# LED_Light_RS232_ZG.net
KiCad netlist of a schematic drawn in EAGLE
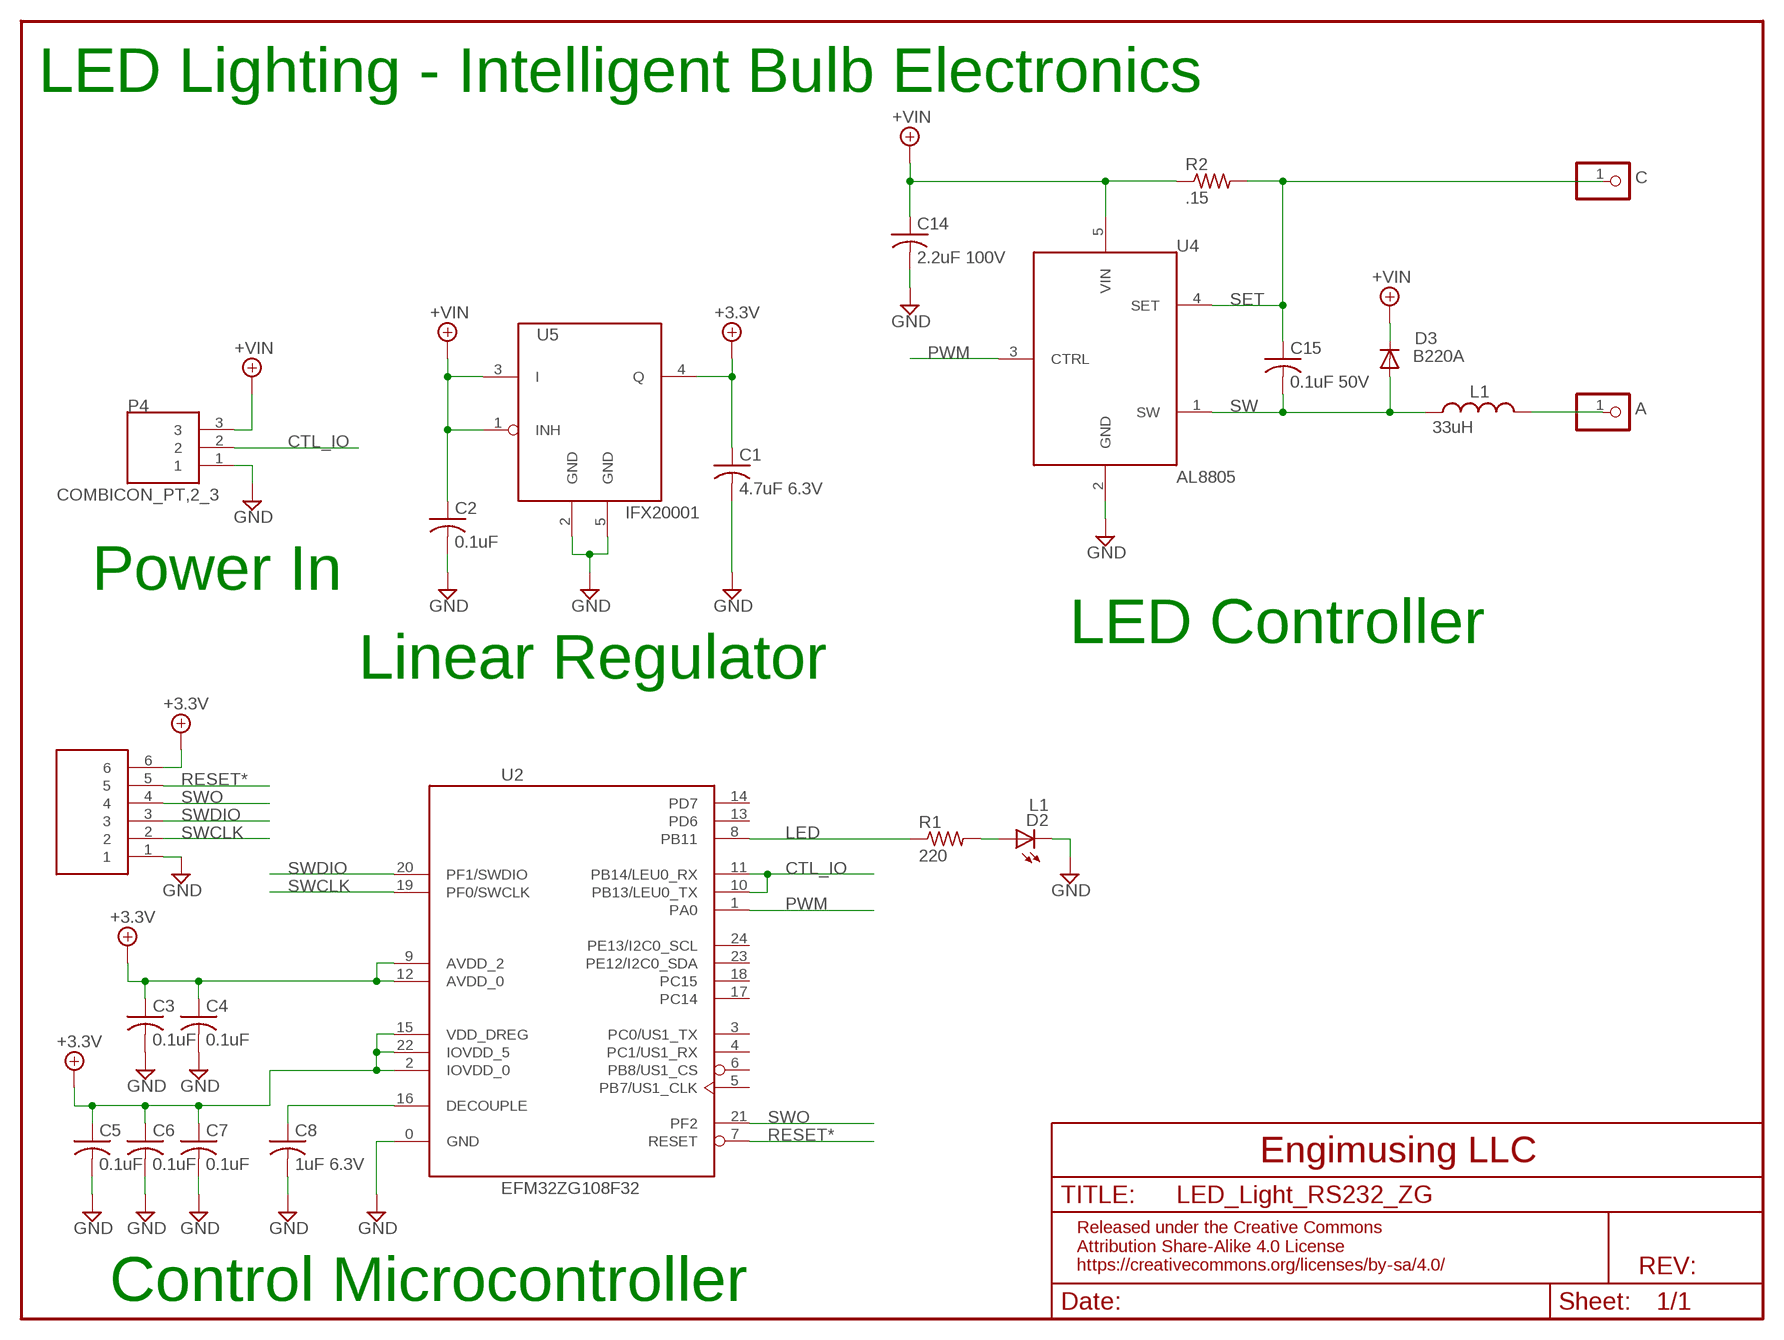
[diagram p0: schematic, sheet 1]

(export (version "E")
  (design (tool "Eeschema 10.0.6"))
  (components
    (comp (ref "A")
      (value "PINHD-1X1")
      (footprint "eagle-import:1X01")
      (libsource (lib "eagle-import") (part "PINHD-1X1"))
    )
    (comp (ref "C")
      (value "PINHD-1X1")
      (footprint "eagle-import:1X01")
      (libsource (lib "eagle-import") (part "PINHD-1X1"))
    )
    (comp (ref "C1")
      (value "4.7uF 6.3V")
      (footprint "eagle-import:C0603")
      (libsource (lib "eagle-import") (part "C-USC0603"))
    )
    (comp (ref "C2")
      (value "0.1uF")
      (footprint "eagle-import:C0603")
      (libsource (lib "eagle-import") (part "C-USC0603"))
    )
    (comp (ref "C3")
      (value "0.1uF")
      (footprint "eagle-import:C0402")
      (libsource (lib "eagle-import") (part "cc_rcl_C-USC0402"))
    )
    (comp (ref "C4")
      (value "0.1uF")
      (footprint "eagle-import:C0402")
      (libsource (lib "eagle-import") (part "cc_rcl_C-USC0402"))
    )
    (comp (ref "C5")
      (value "0.1uF")
      (footprint "eagle-import:C0402")
      (libsource (lib "eagle-import") (part "cc_rcl_C-USC0402"))
    )
    (comp (ref "C6")
      (value "0.1uF")
      (footprint "eagle-import:C0402")
      (libsource (lib "eagle-import") (part "cc_rcl_C-USC0402"))
    )
    (comp (ref "C7")
      (value "0.1uF")
      (footprint "eagle-import:C0402")
      (libsource (lib "eagle-import") (part "cc_rcl_C-USC0402"))
    )
    (comp (ref "C8")
      (value "1uF 6.3V")
      (footprint "eagle-import:C0603")
      (libsource (lib "eagle-import") (part "C-USC0603"))
    )
    (comp (ref "C14")
      (value "2.2uF 100V")
      (footprint "eagle-import:C1210K")
      (libsource (lib "eagle-import") (part "C-USC1210K"))
    )
    (comp (ref "C15")
      (value "0.1uF 50V")
      (footprint "eagle-import:C0603")
      (libsource (lib "eagle-import") (part "cc_rcl_C-USC0603"))
    )
    (comp (ref "D2")
      (value "L1")
      (footprint "eagle-import:CHIP-LED0603")
      (libsource (lib "eagle-import") (part "LEDCHIP-LED0603"))
    )
    (comp (ref "D3")
      (value "B220A")
      (footprint "eagle-import:DO214SMA")
      (libsource (lib "eagle-import") (part "DIODE"))
    )
    (comp (ref "L1")
      (value "33uH")
      (footprint "eagle-import:SRN6045")
      (libsource (lib "eagle-import") (part "INDUCTOR"))
    )
    (comp (ref "P3")
      (value "DF11-6_STRAIGHT_PIN")
      (footprint "eagle-import:DF11SP-6-H")
      (libsource (lib "eagle-import") (part "DF11-6_STRAIGHT_PIN"))
    )
    (comp (ref "P4")
      (value "COMBICON_PT,2_3")
      (footprint "eagle-import:PT_2,5_3-5,0-H")
      (libsource (lib "eagle-import") (part "COMBICON_PT,2_3"))
    )
    (comp (ref "R1")
      (value "220")
      (footprint "eagle-import:R0402")
      (libsource (lib "eagle-import") (part "cc_rcl_R-USR0402"))
    )
    (comp (ref "R2")
      (value ".15")
      (footprint "eagle-import:R0805")
      (libsource (lib "eagle-import") (part "R-USR0805"))
    )
    (comp (ref "U2")
      (value "EFM32ZG108F32")
      (footprint "eagle-import:QFN24_5X5")
      (libsource (lib "eagle-import") (part "EFM32ZG108F32"))
    )
    (comp (ref "U4")
      (value "AL8805")
      (footprint "eagle-import:SOT-23-5A")
      (libsource (lib "eagle-import") (part "AL8805"))
    )
    (comp (ref "U5")
      (value "IFX20001")
      (footprint "eagle-import:PG-SCT595-5")
      (libsource (lib "eagle-import") (part "IFX20001"))
    )
  )
  (nets
    (net (code "1") (name "+3.3V") (class "Default")
      (node (ref "C1") (pin "1") (pinfunction "1_1") (pintype "passive"))
      (node (ref "C3") (pin "1") (pinfunction "1_1") (pintype "passive"))
      (node (ref "C4") (pin "1") (pinfunction "1_1") (pintype "passive"))
      (node (ref "C5") (pin "1") (pinfunction "1_1") (pintype "passive"))
      (node (ref "C6") (pin "1") (pinfunction "1_1") (pintype "passive"))
      (node (ref "C7") (pin "1") (pinfunction "1_1") (pintype "passive"))
      (node (ref "P3") (pin "6") (pinfunction "6_6") (pintype "passive"))
      (node (ref "U2") (pin "12") (pinfunction "AVDD_0_12") (pintype "power_in"))
      (node (ref "U2") (pin "15") (pinfunction "VDD_DREG_15") (pintype "power_in"))
      (node (ref "U2") (pin "2") (pinfunction "IOVDD_0_2") (pintype "power_in"))
      (node (ref "U2") (pin "22") (pinfunction "IOVDD_5_22") (pintype "power_in"))
      (node (ref "U2") (pin "9") (pinfunction "AVDD_2_9") (pintype "power_in"))
      (node (ref "U5") (pin "4") (pinfunction "Q_4") (pintype "power_in"))
    )
    (net (code "2") (name "+VIN") (class "Default")
      (node (ref "C14") (pin "1") (pinfunction "1_1") (pintype "passive"))
      (node (ref "C2") (pin "1") (pinfunction "1_1") (pintype "passive"))
      (node (ref "D3") (pin "1") (pinfunction "C_1") (pintype "passive"))
      (node (ref "P4") (pin "3") (pinfunction "3_3") (pintype "passive"))
      (node (ref "R2") (pin "1") (pinfunction "1_1") (pintype "passive"))
      (node (ref "U4") (pin "5") (pinfunction "VIN_5") (pintype "bidirectional"))
      (node (ref "U5") (pin "1") (pinfunction "INH_1") (pintype "input"))
      (node (ref "U5") (pin "3") (pinfunction "I_3") (pintype "power_in"))
    )
    (net (code "3") (name "/CTL_IO") (class "Default")
      (node (ref "P4") (pin "2") (pinfunction "2_2") (pintype "passive"))
      (node (ref "U2") (pin "10") (pinfunction "PB13/LEU0_TX_10") (pintype "bidirectional"))
      (node (ref "U2") (pin "11") (pinfunction "PB14/LEU0_RX_11") (pintype "bidirectional"))
    )
    (net (code "4") (name "/LED") (class "Default")
      (node (ref "R1") (pin "1") (pinfunction "1_1") (pintype "passive"))
      (node (ref "U2") (pin "8") (pinfunction "PB11_8") (pintype "bidirectional"))
    )
    (net (code "5") (name "/PWM") (class "Default")
      (node (ref "U2") (pin "1") (pinfunction "PA0_1") (pintype "bidirectional"))
      (node (ref "U4") (pin "3") (pinfunction "CTRL_3") (pintype "bidirectional"))
    )
    (net (code "6") (name "/RESET*") (class "Default")
      (node (ref "P3") (pin "5") (pinfunction "5_5") (pintype "passive"))
      (node (ref "U2") (pin "7") (pinfunction "RESET_7") (pintype "input"))
    )
    (net (code "7") (name "/SET") (class "Default")
      (node (ref "C") (pin "1") (pinfunction "1_1") (pintype "passive"))
      (node (ref "C15") (pin "1") (pinfunction "1_1") (pintype "passive"))
      (node (ref "R2") (pin "2") (pinfunction "2_2") (pintype "passive"))
      (node (ref "U4") (pin "4") (pinfunction "SET_4") (pintype "bidirectional"))
    )
    (net (code "8") (name "/SW") (class "Default")
      (node (ref "C15") (pin "2") (pinfunction "2_2") (pintype "passive"))
      (node (ref "D3") (pin "2") (pinfunction "A_2") (pintype "passive"))
      (node (ref "L1") (pin "1") (pinfunction "1_1") (pintype "passive"))
      (node (ref "U4") (pin "1") (pinfunction "SW_1") (pintype "bidirectional"))
    )
    (net (code "9") (name "/SWCLK") (class "Default")
      (node (ref "P3") (pin "2") (pinfunction "2_2") (pintype "passive"))
      (node (ref "U2") (pin "19") (pinfunction "PF0/SWCLK_19") (pintype "bidirectional"))
    )
    (net (code "10") (name "/SWDIO") (class "Default")
      (node (ref "P3") (pin "3") (pinfunction "3_3") (pintype "passive"))
      (node (ref "U2") (pin "20") (pinfunction "PF1/SWDIO_20") (pintype "bidirectional"))
    )
    (net (code "11") (name "/SWO") (class "Default")
      (node (ref "P3") (pin "4") (pinfunction "4_4") (pintype "passive"))
      (node (ref "U2") (pin "21") (pinfunction "PF2_21") (pintype "bidirectional"))
    )
    (net (code "12") (name "GND") (class "Default")
      (node (ref "C1") (pin "2") (pinfunction "2_2") (pintype "passive"))
      (node (ref "C14") (pin "2") (pinfunction "2_2") (pintype "passive"))
      (node (ref "C2") (pin "2") (pinfunction "2_2") (pintype "passive"))
      (node (ref "C3") (pin "2") (pinfunction "2_2") (pintype "passive"))
      (node (ref "C4") (pin "2") (pinfunction "2_2") (pintype "passive"))
      (node (ref "C5") (pin "2") (pinfunction "2_2") (pintype "passive"))
      (node (ref "C6") (pin "2") (pinfunction "2_2") (pintype "passive"))
      (node (ref "C7") (pin "2") (pinfunction "2_2") (pintype "passive"))
      (node (ref "C8") (pin "2") (pinfunction "2_2") (pintype "passive"))
      (node (ref "D2") (pin "C") (pinfunction "C_C") (pintype "passive"))
      (node (ref "P3") (pin "1") (pinfunction "1_1") (pintype "passive"))
      (node (ref "P4") (pin "1") (pinfunction "1_1") (pintype "passive"))
      (node (ref "U2") (pin "0") (pinfunction "GND_0") (pintype "power_in"))
      (node (ref "U4") (pin "2") (pinfunction "GND_2") (pintype "bidirectional"))
      (node (ref "U5") (pin "2") (pinfunction "GND_2") (pintype "bidirectional"))
      (node (ref "U5") (pin "5") (pinfunction "GND_5") (pintype "bidirectional"))
    )
    (net (code "13") (name "Net-(A-Pad1)") (class "Default")
      (node (ref "A") (pin "1") (pinfunction "1_1") (pintype "passive"))
      (node (ref "L1") (pin "2") (pinfunction "2_2") (pintype "passive"))
    )
    (net (code "14") (name "Net-(D2-PadA)") (class "Default")
      (node (ref "D2") (pin "A") (pinfunction "A_A") (pintype "passive"))
      (node (ref "R1") (pin "2") (pinfunction "2_2") (pintype "passive"))
    )
    (net (code "15") (name "Net-(U2-DECOUPLE)") (class "Default")
      (node (ref "C8") (pin "1") (pinfunction "1_1") (pintype "passive"))
      (node (ref "U2") (pin "16") (pinfunction "DECOUPLE_16") (pintype "passive"))
    )
    (net (code "16") (name "unconnected-(U2-PB7{slash}US1_CLK-Pad5)") (class "Default")
      (node (ref "U2") (pin "5") (pinfunction "PB7/US1_CLK_5") (pintype "bidirectional"))
    )
    (net (code "17") (name "unconnected-(U2-PB8{slash}US1_CS-Pad6)") (class "Default")
      (node (ref "U2") (pin "6") (pinfunction "PB8/US1_CS_6") (pintype "bidirectional"))
    )
    (net (code "18") (name "unconnected-(U2-PC0{slash}US1_TX-Pad3)") (class "Default")
      (node (ref "U2") (pin "3") (pinfunction "PC0/US1_TX_3") (pintype "bidirectional"))
    )
    (net (code "19") (name "unconnected-(U2-PC1{slash}US1_RX-Pad4)") (class "Default")
      (node (ref "U2") (pin "4") (pinfunction "PC1/US1_RX_4") (pintype "bidirectional"))
    )
    (net (code "20") (name "unconnected-(U2-PC14-Pad17)") (class "Default")
      (node (ref "U2") (pin "17") (pinfunction "PC14_17") (pintype "bidirectional"))
    )
    (net (code "21") (name "unconnected-(U2-PC15-Pad18)") (class "Default")
      (node (ref "U2") (pin "18") (pinfunction "PC15_18") (pintype "bidirectional"))
    )
    (net (code "22") (name "unconnected-(U2-PD6-Pad13)") (class "Default")
      (node (ref "U2") (pin "13") (pinfunction "PD6_13") (pintype "bidirectional"))
    )
    (net (code "23") (name "unconnected-(U2-PD7-Pad14)") (class "Default")
      (node (ref "U2") (pin "14") (pinfunction "PD7_14") (pintype "bidirectional"))
    )
    (net (code "24") (name "unconnected-(U2-PE12{slash}I2C0_SDA-Pad23)") (class "Default")
      (node (ref "U2") (pin "23") (pinfunction "PE12/I2C0_SDA_23") (pintype "bidirectional"))
    )
    (net (code "25") (name "unconnected-(U2-PE13{slash}I2C0_SCL-Pad24)") (class "Default")
      (node (ref "U2") (pin "24") (pinfunction "PE13/I2C0_SCL_24") (pintype "bidirectional"))
    )
  )
)
